# LED_sch.net
KiCad netlist of a schematic drawn in Altium Designer
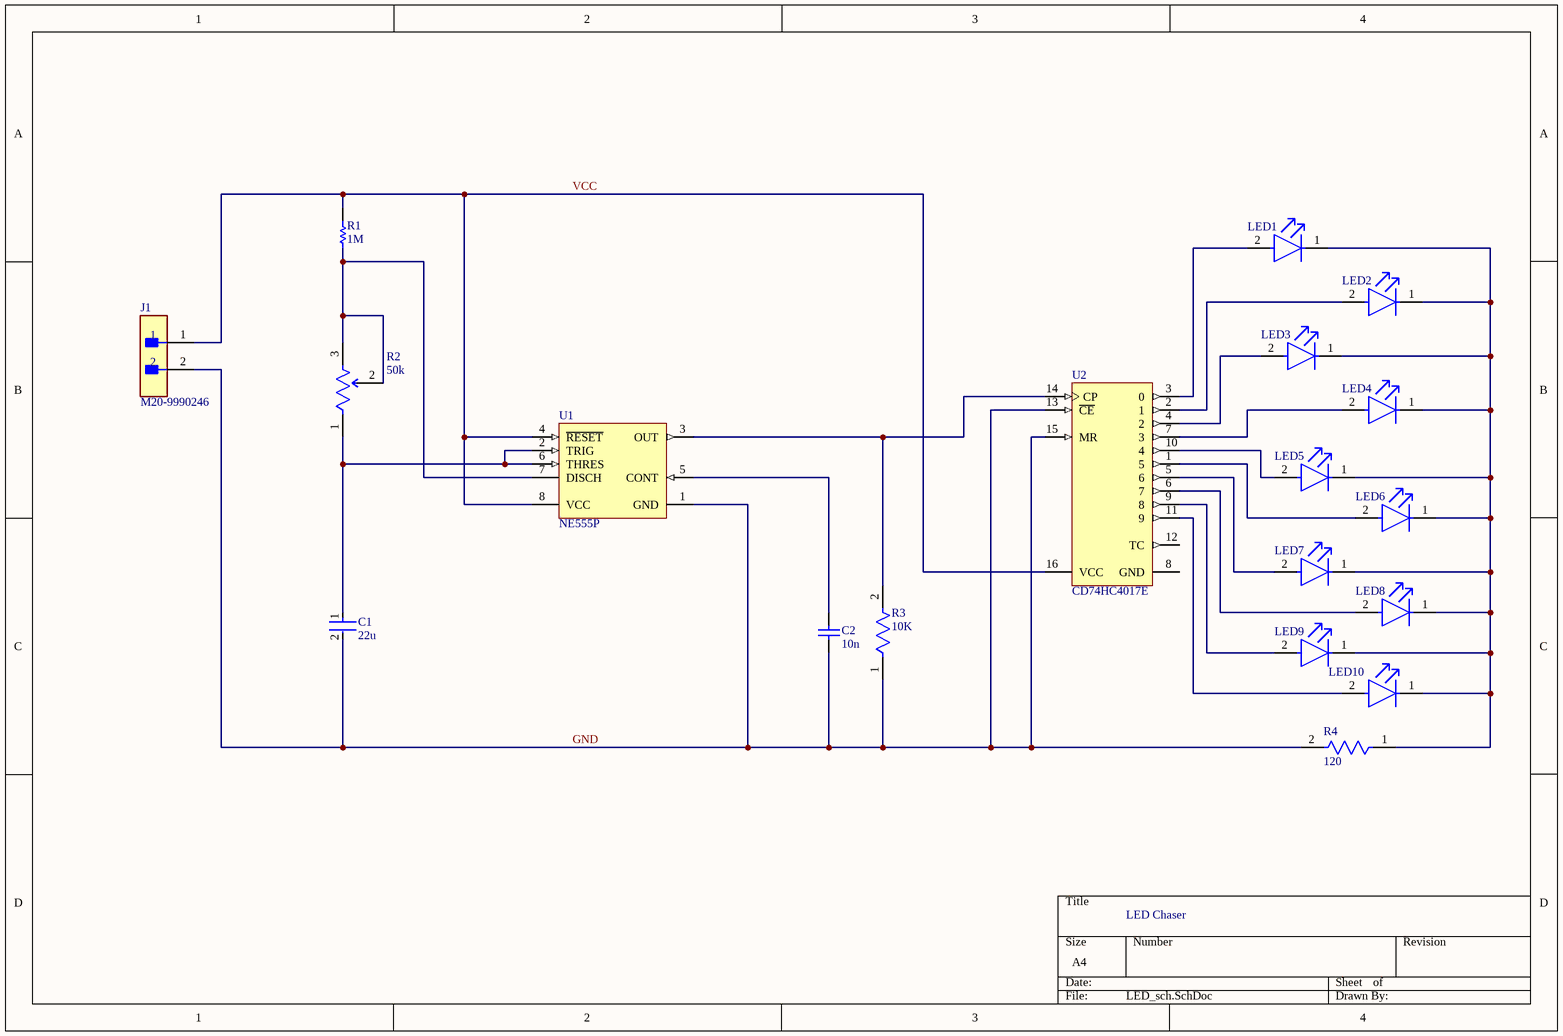
[diagram p0: LED_sch.SchDoc]

(export (version "E")
  (design (tool "Eeschema 10.0.6"))
  (components
    (comp (ref "C1")
      (value "22u")
      (footprint "FP-1206-L_3_2_0_2-W_1_6_0-IPC_C")
      (description "General Purpose Ceramic Capacitor, 1206, 22uF, 10%, X5R, 15%, 6.3V")
      (fields (field (name "TOLERANCE") "10%") (field (name "VOLTAGE") "6.3V"))
      (libsource (lib "Altium Content Vault") (part "02cd4be3c70576c341d710602a673aa"))
    )
    (comp (ref "C2")
      (value "10n")
      (footprint "CAPC1608X92X38NL15T08")
      (fields (field (name "PART NUMBER") "VJ0603Y103KXBAC") (field (name "MANUFACTURER") "Vitramon"))
      (libsource (lib "Altium Content Vault") (part "CAP"))
    )
    (comp (ref "J1")
      (value "M20-9990246")
      (footprint "FP-M20-9990246-MFG")
      (description "CONN HEADER VERT 2POS 2.54MM")
      (fields
        (field (name "OCTOPART") "https://octopart.com/m20-9990246-harwin-2590635")
        (field (name "MANUFACTURER") "Harwin")
      )
      (libsource (lib "Altium Content Vault") (part "3bc925449376181038e59eaffc5286c"))
    )
    (comp (ref "LED1")
      (value "HLMP-P156-HK011")
      (footprint "FP-HLMP-P156-HK011-MFG")
      (description "LED RED CLEAR FLAT 2SMD GW")
      (fields
        (field (name "OCTOPART") "https://octopart.com/hlmp-p156-hk011-broadcom-78782124")
        (field (name "MANUFACTURER") "Broadcom Limited")
      )
      (libsource (lib "Altium Content Vault") (part "8706943c75ba83719d021d2fdc84c58"))
    )
    (comp (ref "LED2")
      (value "HLMP-P156-HK011")
      (footprint "FP-HLMP-P156-HK011-MFG")
      (description "LED RED CLEAR FLAT 2SMD GW")
      (fields
        (field (name "OCTOPART") "https://octopart.com/hlmp-p156-hk011-broadcom-78782124")
        (field (name "MANUFACTURER") "Broadcom Limited")
      )
      (libsource (lib "Altium Content Vault") (part "8706943c75ba83719d021d2fdc84c58"))
    )
    (comp (ref "LED3")
      (value "HLMP-P156-HK011")
      (footprint "FP-HLMP-P156-HK011-MFG")
      (description "LED RED CLEAR FLAT 2SMD GW")
      (fields
        (field (name "OCTOPART") "https://octopart.com/hlmp-p156-hk011-broadcom-78782124")
        (field (name "MANUFACTURER") "Broadcom Limited")
      )
      (libsource (lib "Altium Content Vault") (part "8706943c75ba83719d021d2fdc84c58"))
    )
    (comp (ref "LED4")
      (value "HLMP-P156-HK011")
      (footprint "FP-HLMP-P156-HK011-MFG")
      (description "LED RED CLEAR FLAT 2SMD GW")
      (fields
        (field (name "OCTOPART") "https://octopart.com/hlmp-p156-hk011-broadcom-78782124")
        (field (name "MANUFACTURER") "Broadcom Limited")
      )
      (libsource (lib "Altium Content Vault") (part "8706943c75ba83719d021d2fdc84c58"))
    )
    (comp (ref "LED5")
      (value "HLMP-P156-HK011")
      (footprint "FP-HLMP-P156-HK011-MFG")
      (description "LED RED CLEAR FLAT 2SMD GW")
      (fields
        (field (name "OCTOPART") "https://octopart.com/hlmp-p156-hk011-broadcom-78782124")
        (field (name "MANUFACTURER") "Broadcom Limited")
      )
      (libsource (lib "Altium Content Vault") (part "8706943c75ba83719d021d2fdc84c58"))
    )
    (comp (ref "LED6")
      (value "HLMP-P156-HK011")
      (footprint "FP-HLMP-P156-HK011-MFG")
      (description "LED RED CLEAR FLAT 2SMD GW")
      (fields
        (field (name "OCTOPART") "https://octopart.com/hlmp-p156-hk011-broadcom-78782124")
        (field (name "MANUFACTURER") "Broadcom Limited")
      )
      (libsource (lib "Altium Content Vault") (part "8706943c75ba83719d021d2fdc84c58"))
    )
    (comp (ref "LED7")
      (value "HLMP-P156-HK011")
      (footprint "FP-HLMP-P156-HK011-MFG")
      (description "LED RED CLEAR FLAT 2SMD GW")
      (fields
        (field (name "OCTOPART") "https://octopart.com/hlmp-p156-hk011-broadcom-78782124")
        (field (name "MANUFACTURER") "Broadcom Limited")
      )
      (libsource (lib "Altium Content Vault") (part "8706943c75ba83719d021d2fdc84c58"))
    )
    (comp (ref "LED8")
      (value "HLMP-P156-HK011")
      (footprint "FP-HLMP-P156-HK011-MFG")
      (description "LED RED CLEAR FLAT 2SMD GW")
      (fields
        (field (name "OCTOPART") "https://octopart.com/hlmp-p156-hk011-broadcom-78782124")
        (field (name "MANUFACTURER") "Broadcom Limited")
      )
      (libsource (lib "Altium Content Vault") (part "8706943c75ba83719d021d2fdc84c58"))
    )
    (comp (ref "LED9")
      (value "HLMP-P156-HK011")
      (footprint "FP-HLMP-P156-HK011-MFG")
      (description "LED RED CLEAR FLAT 2SMD GW")
      (fields
        (field (name "OCTOPART") "https://octopart.com/hlmp-p156-hk011-broadcom-78782124")
        (field (name "MANUFACTURER") "Broadcom Limited")
      )
      (libsource (lib "Altium Content Vault") (part "8706943c75ba83719d021d2fdc84c58"))
    )
    (comp (ref "LED10")
      (value "HLMP-P156-HK011")
      (footprint "FP-HLMP-P156-HK011-MFG")
      (description "LED RED CLEAR FLAT 2SMD GW")
      (fields
        (field (name "OCTOPART") "https://octopart.com/hlmp-p156-hk011-broadcom-78782124")
        (field (name "MANUFACTURER") "Broadcom Limited")
      )
      (libsource (lib "Altium Content Vault") (part "8706943c75ba83719d021d2fdc84c58"))
    )
    (comp (ref "R1")
      (value "1M")
      (footprint "RESA60-630X240")
      (description "Axial Resistor, 1 MOhm, +/- 1%, 250 mW, -55 to 155 degC, 2-Pin THD, RoHS, Bulk")
      (fields (field (name "TOLERANCE") "1%"))
      (libsource (lib "Altium Content Vault") (part "RES-2"))
    )
    (comp (ref "R2")
      (value "50k")
      (footprint "FP-3362P-1-503TLF-MFG")
      (description "TRIMMER 50K OHM 0.5W PC PIN TOP")
      (fields (field (name "TOLERANCE") "10%"))
      (libsource (lib "Altium Content Vault") (part "2dcfd2547301a7d3209a5e99acfd772"))
    )
    (comp (ref "R3")
      (value "10K")
      (footprint "FP-MFR-12-MFG")
      (description "RES MF 1/6W 1% AXIAL")
      (fields (field (name "TOLERANCE") "1%"))
      (libsource (lib "Altium Content Vault") (part "1029c3af85768c4190bb7ad29bc67b5"))
    )
    (comp (ref "R4")
      (value "120")
      (footprint "FP-MRS1600-MFG")
      (description "RES 120 OHM 1% 0.4W AXIAL")
      (fields (field (name "TOLERANCE") "1%"))
      (libsource (lib "Altium Content Vault") (part "1029c3af85768c4190bb7ad29bc67b5"))
    )
    (comp (ref "U1")
      (value "NE555P")
      (footprint "P0008A")
      (description "Precision Timer, 4.5 to 16 V, 0 to 70 degC, 8-Pin DIP, Pb-Free, Tube")
      (fields (field (name "MANUFACTURER") "TexasInstruments"))
      (libsource (lib "Altium Content Vault") (part "TI-NE555-P8"))
    )
    (comp (ref "U2")
      (value "CD74HC4017E")
      (footprint "N0016A")
      (description "High Speed CMOS Logic Decade Counter/Divider with 10 Decoded Outputs, N0016A, TUBE")
      (fields
        (field (name "GENERIC PART NUMBER") "CD74HC4017")
        (field (name "MANUFACTURER") "Texas Instruments")
      )
      (libsource (lib "Altium Content Vault") (part "TI-CD74HC4017-16"))
    )
  )
  (nets
    (net (code "1") (name "/GND") (class "Default")
      (node (ref "C1") (pin "2") (pinfunction "2_2") (pintype "passive"))
      (node (ref "C2") (pin "1") (pinfunction "1_1") (pintype "passive"))
      (node (ref "J1") (pin "2") (pinfunction "2_2") (pintype "passive"))
      (node (ref "R3") (pin "1") (pinfunction "1_1") (pintype "passive"))
      (node (ref "R4") (pin "2") (pinfunction "2_2") (pintype "passive"))
      (node (ref "U1") (pin "1") (pinfunction "GND_1") (pintype "power_in"))
      (node (ref "U2") (pin "13") (pinfunction "~{CE}_13") (pintype "input"))
      (node (ref "U2") (pin "15") (pinfunction "MR_15") (pintype "input"))
    )
    (net (code "2") (name "/VCC") (class "Default")
      (node (ref "J1") (pin "1") (pinfunction "1_1") (pintype "passive"))
      (node (ref "R1") (pin "2") (pinfunction "2_2") (pintype "passive"))
      (node (ref "U1") (pin "4") (pinfunction "~{RESET}_4") (pintype "input"))
      (node (ref "U1") (pin "8") (pinfunction "VCC_8") (pintype "power_in"))
      (node (ref "U2") (pin "16") (pinfunction "VCC_16") (pintype "power_in"))
    )
    (net (code "3") (name "Net-(LED1-A)") (class "Default")
      (node (ref "LED1") (pin "2") (pinfunction "A_2") (pintype "passive"))
      (node (ref "U2") (pin "3") (pinfunction "0_3") (pintype "output"))
    )
    (net (code "4") (name "Net-(LED1-C)") (class "Default")
      (node (ref "LED1") (pin "1") (pinfunction "C_1") (pintype "passive"))
      (node (ref "LED10") (pin "1") (pinfunction "C_1") (pintype "passive"))
      (node (ref "LED2") (pin "1") (pinfunction "C_1") (pintype "passive"))
      (node (ref "LED3") (pin "1") (pinfunction "C_1") (pintype "passive"))
      (node (ref "LED4") (pin "1") (pinfunction "C_1") (pintype "passive"))
      (node (ref "LED5") (pin "1") (pinfunction "C_1") (pintype "passive"))
      (node (ref "LED6") (pin "1") (pinfunction "C_1") (pintype "passive"))
      (node (ref "LED7") (pin "1") (pinfunction "C_1") (pintype "passive"))
      (node (ref "LED8") (pin "1") (pinfunction "C_1") (pintype "passive"))
      (node (ref "LED9") (pin "1") (pinfunction "C_1") (pintype "passive"))
      (node (ref "R4") (pin "1") (pinfunction "1_1") (pintype "passive"))
    )
    (net (code "5") (name "Net-(LED2-A)") (class "Default")
      (node (ref "LED2") (pin "2") (pinfunction "A_2") (pintype "passive"))
      (node (ref "U2") (pin "2") (pinfunction "1_2") (pintype "output"))
    )
    (net (code "6") (name "Net-(LED3-A)") (class "Default")
      (node (ref "LED3") (pin "2") (pinfunction "A_2") (pintype "passive"))
      (node (ref "U2") (pin "4") (pinfunction "2_4") (pintype "output"))
    )
    (net (code "7") (name "Net-(LED4-A)") (class "Default")
      (node (ref "LED4") (pin "2") (pinfunction "A_2") (pintype "passive"))
      (node (ref "U2") (pin "7") (pinfunction "3_7") (pintype "output"))
    )
    (net (code "8") (name "Net-(LED5-A)") (class "Default")
      (node (ref "LED5") (pin "2") (pinfunction "A_2") (pintype "passive"))
      (node (ref "U2") (pin "10") (pinfunction "4_10") (pintype "output"))
    )
    (net (code "9") (name "Net-(LED6-A)") (class "Default")
      (node (ref "LED6") (pin "2") (pinfunction "A_2") (pintype "passive"))
      (node (ref "U2") (pin "1") (pinfunction "5_1") (pintype "output"))
    )
    (net (code "10") (name "Net-(LED7-A)") (class "Default")
      (node (ref "LED7") (pin "2") (pinfunction "A_2") (pintype "passive"))
      (node (ref "U2") (pin "5") (pinfunction "6_5") (pintype "output"))
    )
    (net (code "11") (name "Net-(LED8-A)") (class "Default")
      (node (ref "LED8") (pin "2") (pinfunction "A_2") (pintype "passive"))
      (node (ref "U2") (pin "6") (pinfunction "7_6") (pintype "output"))
    )
    (net (code "12") (name "Net-(LED9-A)") (class "Default")
      (node (ref "LED9") (pin "2") (pinfunction "A_2") (pintype "passive"))
      (node (ref "U2") (pin "9") (pinfunction "8_9") (pintype "output"))
    )
    (net (code "13") (name "Net-(LED10-A)") (class "Default")
      (node (ref "LED10") (pin "2") (pinfunction "A_2") (pintype "passive"))
      (node (ref "U2") (pin "11") (pinfunction "9_11") (pintype "output"))
    )
    (net (code "14") (name "Net-(R2-CCW)") (class "Default")
      (node (ref "C1") (pin "1") (pinfunction "1_1") (pintype "passive"))
      (node (ref "R2") (pin "1") (pinfunction "CCW_1") (pintype "passive"))
      (node (ref "U1") (pin "2") (pinfunction "TRIG_2") (pintype "input"))
      (node (ref "U1") (pin "6") (pinfunction "THRES_6") (pintype "input"))
    )
    (net (code "15") (name "Net-(R2-CW)") (class "Default")
      (node (ref "R1") (pin "1") (pinfunction "1_1") (pintype "passive"))
      (node (ref "R2") (pin "2") (pinfunction "WIPER_2") (pintype "passive"))
      (node (ref "R2") (pin "3") (pinfunction "CW_3") (pintype "passive"))
      (node (ref "U1") (pin "7") (pinfunction "DISCH_7") (pintype "open_collector"))
    )
    (net (code "16") (name "Net-(U1-CONT)") (class "Default")
      (node (ref "C2") (pin "2") (pinfunction "2_2") (pintype "passive"))
      (node (ref "U1") (pin "5") (pinfunction "CONT_5") (pintype "input"))
    )
    (net (code "17") (name "Net-(U1-OUT)") (class "Default")
      (node (ref "R3") (pin "2") (pinfunction "2_2") (pintype "passive"))
      (node (ref "U1") (pin "3") (pinfunction "OUT_3") (pintype "output"))
      (node (ref "U2") (pin "14") (pinfunction "CP_14") (pintype "input"))
    )
    (net (code "18") (name "unconnected-(U2-GND-Pad8)") (class "Default")
      (node (ref "U2") (pin "8") (pinfunction "GND_8") (pintype "power_in"))
    )
    (net (code "19") (name "unconnected-(U2-TC-Pad12)") (class "Default")
      (node (ref "U2") (pin "12") (pinfunction "TC_12") (pintype "output"))
    )
  )
)
